# MCU.net
KiCad netlist of a schematic drawn in Altium Designer
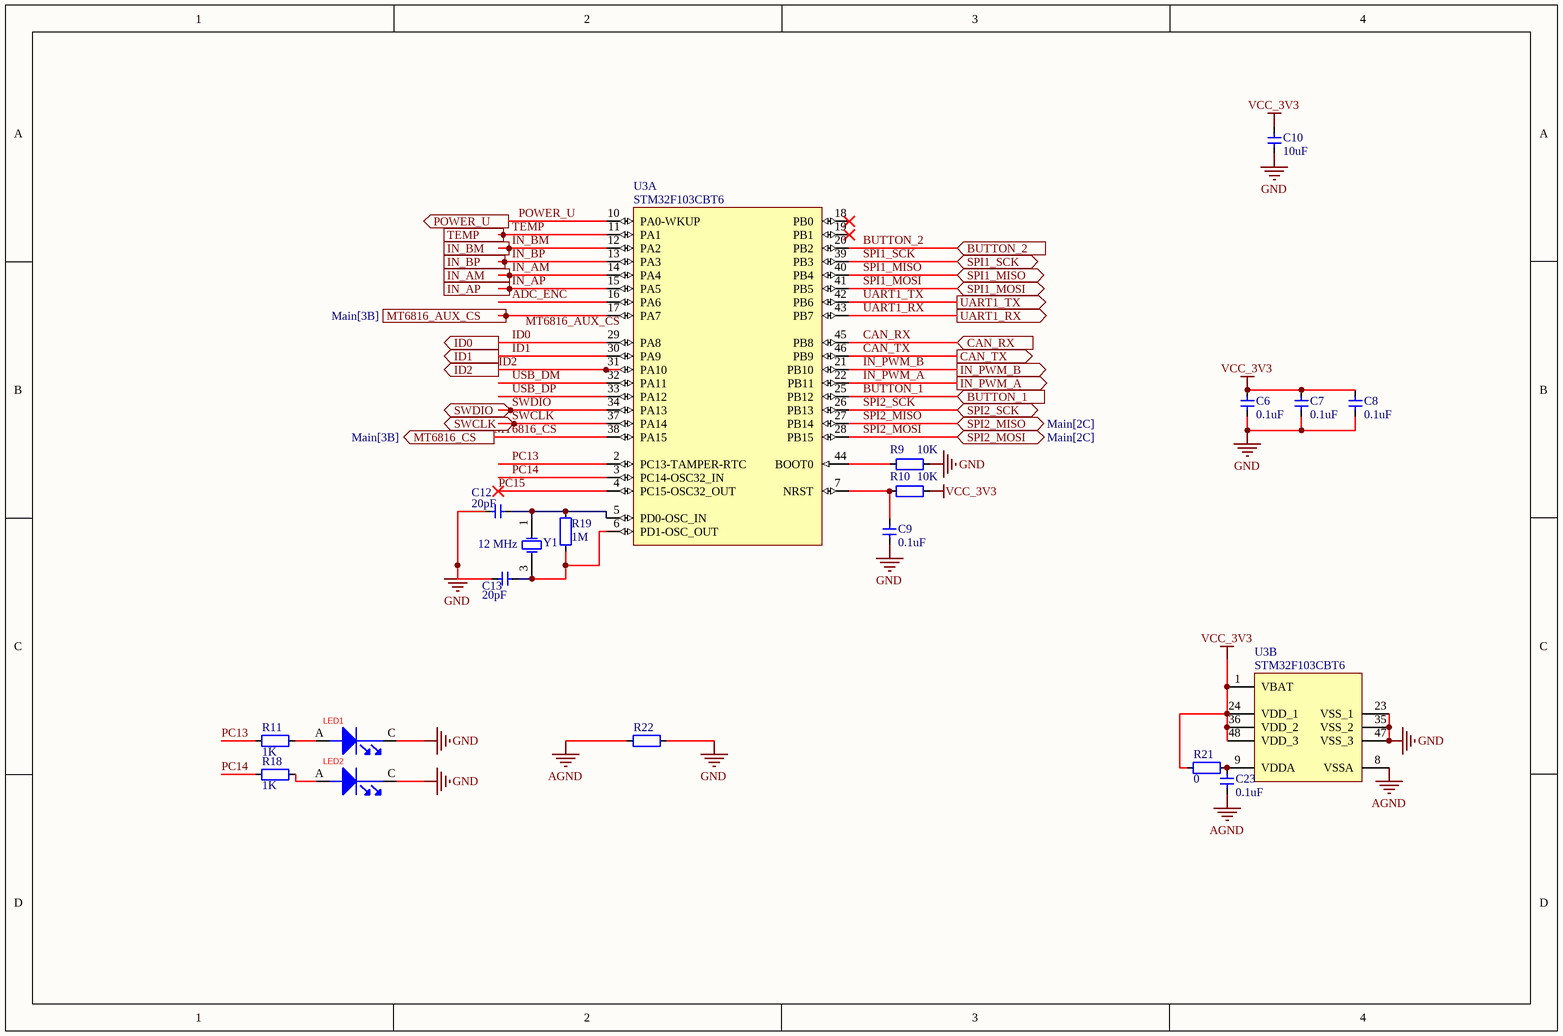
[diagram p0: MCU.SchDoc]

(export (version "E")
  (design (tool "Eeschema 10.0.6"))
  (components
    (comp (ref "C6")
      (value "0.1uF")
      (footprint "motor42-lib:CAP_0402")
      (description "Capacitor")
      (libsource (lib "MyPcbLib") (part "电容-0402"))
    )
    (comp (ref "C7")
      (value "0.1uF")
      (footprint "motor42-lib:CAP_0402")
      (description "Capacitor")
      (libsource (lib "MyPcbLib") (part "电容-0402"))
    )
    (comp (ref "C8")
      (value "0.1uF")
      (footprint "motor42-lib:CAP_0402")
      (description "Capacitor")
      (libsource (lib "MyPcbLib") (part "电容-0402"))
    )
    (comp (ref "C9")
      (value "0.1uF")
      (footprint "motor42-lib:CAP_0402")
      (description "Capacitor")
      (libsource (lib "MyPcbLib") (part "电容-0402"))
    )
    (comp (ref "C10")
      (value "10uF")
      (footprint "CAP_0402")
      (description "Capacitor")
      (libsource (lib "MyPcbLib") (part "电容-0402"))
    )
    (comp (ref "C12")
      (value "20pF")
      (footprint "motor42-lib:CAP_0402")
      (description "Capacitor")
      (libsource (lib "MyPcbLib") (part "电容-0402"))
    )
    (comp (ref "C13")
      (value "20pF")
      (footprint "motor42-lib:CAP_0402")
      (description "Capacitor")
      (libsource (lib "MyPcbLib") (part "电容-0402"))
    )
    (comp (ref "C23")
      (value "0.1uF")
      (footprint "motor42-lib:CAP_0402")
      (description "Capacitor")
      (libsource (lib "MyPcbLib") (part "电容-0402"))
    )
    (comp (ref "LED1")
      (value "LED GREEN")
      (footprint "LED-0603")
      (description "LED GRN SGL RA 25mA 4.1V SMD")
      (libsource (lib "*") (part "LED"))
    )
    (comp (ref "LED2")
      (value "LED GREEN")
      (footprint "LED-0603")
      (description "LED GRN SGL RA 25mA 4.1V SMD")
      (libsource (lib "*") (part "LED"))
    )
    (comp (ref "R9")
      (value "10K")
      (footprint "RES_0402")
      (description "Resistor")
      (libsource (lib "MyPcbLib") (part "电阻-0402"))
    )
    (comp (ref "R10")
      (value "10K")
      (footprint "RES_0402")
      (description "Resistor")
      (libsource (lib "MyPcbLib") (part "电阻-0402"))
    )
    (comp (ref "R11")
      (value "1K")
      (footprint "RES_0402")
      (description "Resistor")
      (libsource (lib "MyPcbLib") (part "电阻-0402"))
    )
    (comp (ref "R18")
      (value "1K")
      (footprint "RES_0402")
      (description "Resistor")
      (libsource (lib "MyPcbLib") (part "电阻-0402"))
    )
    (comp (ref "R19")
      (value "1M")
      (footprint "RES_0402")
      (description "Resistor")
      (libsource (lib "") (part "电阻-0402_1"))
    )
    (comp (ref "R21")
      (value "0")
      (footprint "RES_0402")
      (description "Resistor")
      (libsource (lib "") (part "电阻-0402_2"))
    )
    (comp (ref "R22")
      (value "0")
      (footprint "RES_0402")
      (description "Resistor")
      (libsource (lib "") (part "电阻-0402_2"))
    )
    (comp (ref "U3")
      (value "STM32F103CBT6")
      (footprint "LQFP-48")
      (libsource (lib "STMicroelectronics STM32 F1") (part "STM32F103CBT6"))
    )
    (comp (ref "Y1")
      (value "12 MHz")
      (footprint "LC-SMD-3225_4P")
      (description "Crystal")
      (fields (field (name "Comment") "XTAL-4"))
      (libsource (lib "rpi") (part "XTAL-4"))
    )
  )
  (nets
    (net (code "1") (name "/ADC_ENC") (class "Default")
      (node (ref "U3") (pin "16") (pinfunction "PA6_16") (pintype "bidirectional"))
    )
    (net (code "2") (name "/BUTTON_1") (class "Default")
      (node (ref "U3") (pin "25") (pinfunction "PB12_25") (pintype "bidirectional"))
    )
    (net (code "3") (name "/BUTTON_2") (class "Default")
      (node (ref "U3") (pin "20") (pinfunction "PB2_20") (pintype "bidirectional"))
    )
    (net (code "4") (name "/CAN_RX") (class "Default")
      (node (ref "U3") (pin "45") (pinfunction "PB8_45") (pintype "bidirectional"))
    )
    (net (code "5") (name "/CAN_TX") (class "Default")
      (node (ref "U3") (pin "46") (pinfunction "PB9_46") (pintype "bidirectional"))
    )
    (net (code "6") (name "/ID0") (class "Default")
      (node (ref "U3") (pin "29") (pinfunction "PA8_29") (pintype "bidirectional"))
    )
    (net (code "7") (name "/ID1") (class "Default")
      (node (ref "U3") (pin "30") (pinfunction "PA9_30") (pintype "bidirectional"))
    )
    (net (code "8") (name "/ID2") (class "Default")
      (node (ref "U3") (pin "31") (pinfunction "PA10_31") (pintype "bidirectional"))
    )
    (net (code "9") (name "/IN_AM") (class "Default")
      (node (ref "U3") (pin "14") (pinfunction "PA4_14") (pintype "bidirectional"))
    )
    (net (code "10") (name "/IN_AP") (class "Default")
      (node (ref "U3") (pin "15") (pinfunction "PA5_15") (pintype "bidirectional"))
    )
    (net (code "11") (name "/IN_BM") (class "Default")
      (node (ref "U3") (pin "12") (pinfunction "PA2_12") (pintype "bidirectional"))
    )
    (net (code "12") (name "/IN_BP") (class "Default")
      (node (ref "U3") (pin "13") (pinfunction "PA3_13") (pintype "bidirectional"))
    )
    (net (code "13") (name "/IN_PWM_A") (class "Default")
      (node (ref "U3") (pin "22") (pinfunction "PB11_22") (pintype "bidirectional"))
    )
    (net (code "14") (name "/IN_PWM_B") (class "Default")
      (node (ref "U3") (pin "21") (pinfunction "PB10_21") (pintype "bidirectional"))
    )
    (net (code "15") (name "/MT6816_AUX_CS") (class "Default")
      (node (ref "U3") (pin "17") (pinfunction "PA7_17") (pintype "bidirectional"))
    )
    (net (code "16") (name "/MT6816_CS") (class "Default")
      (node (ref "U3") (pin "38") (pinfunction "PA15_38") (pintype "bidirectional"))
    )
    (net (code "17") (name "/PC13") (class "Default")
      (node (ref "R11") (pin "1") (pinfunction "1_1") (pintype "passive"))
      (node (ref "U3") (pin "2") (pinfunction "PC13-TAMPER-RTC_2") (pintype "bidirectional"))
    )
    (net (code "18") (name "/PC14") (class "Default")
      (node (ref "R18") (pin "1") (pinfunction "1_1") (pintype "passive"))
      (node (ref "U3") (pin "3") (pinfunction "PC14-OSC32_IN_3") (pintype "bidirectional"))
    )
    (net (code "19") (name "/PC15") (class "Default")
      (node (ref "U3") (pin "4") (pinfunction "PC15-OSC32_OUT_4") (pintype "bidirectional+no_connect"))
    )
    (net (code "20") (name "/POWER_U") (class "Default")
      (node (ref "U3") (pin "10") (pinfunction "PA0-WKUP_10") (pintype "bidirectional"))
    )
    (net (code "21") (name "/SPI1_MISO") (class "Default")
      (node (ref "U3") (pin "40") (pinfunction "PB4_40") (pintype "bidirectional"))
    )
    (net (code "22") (name "/SPI1_MOSI") (class "Default")
      (node (ref "U3") (pin "41") (pinfunction "PB5_41") (pintype "bidirectional"))
    )
    (net (code "23") (name "/SPI1_SCK") (class "Default")
      (node (ref "U3") (pin "39") (pinfunction "PB3_39") (pintype "bidirectional"))
    )
    (net (code "24") (name "/SPI2_MISO") (class "Default")
      (node (ref "U3") (pin "27") (pinfunction "PB14_27") (pintype "bidirectional"))
    )
    (net (code "25") (name "/SPI2_MOSI") (class "Default")
      (node (ref "U3") (pin "28") (pinfunction "PB15_28") (pintype "bidirectional"))
    )
    (net (code "26") (name "/SPI2_SCK") (class "Default")
      (node (ref "U3") (pin "26") (pinfunction "PB13_26") (pintype "bidirectional"))
    )
    (net (code "27") (name "/SWCLK") (class "Default")
      (node (ref "U3") (pin "37") (pinfunction "PA14_37") (pintype "bidirectional"))
    )
    (net (code "28") (name "/SWDIO") (class "Default")
      (node (ref "U3") (pin "34") (pinfunction "PA13_34") (pintype "bidirectional"))
    )
    (net (code "29") (name "/TEMP") (class "Default")
      (node (ref "U3") (pin "11") (pinfunction "PA1_11") (pintype "bidirectional"))
    )
    (net (code "30") (name "/UART1_RX") (class "Default")
      (node (ref "U3") (pin "43") (pinfunction "PB7_43") (pintype "bidirectional"))
    )
    (net (code "31") (name "/UART1_TX") (class "Default")
      (node (ref "U3") (pin "42") (pinfunction "PB6_42") (pintype "bidirectional"))
    )
    (net (code "32") (name "/USB_DM") (class "Default")
      (node (ref "U3") (pin "32") (pinfunction "PA11_32") (pintype "bidirectional"))
    )
    (net (code "33") (name "/USB_DP") (class "Default")
      (node (ref "U3") (pin "33") (pinfunction "PA12_33") (pintype "bidirectional"))
    )
    (net (code "34") (name "AGND") (class "Default")
      (node (ref "C23") (pin "1") (pinfunction "1_1") (pintype "passive"))
      (node (ref "R22") (pin "2") (pinfunction "2_2") (pintype "passive"))
      (node (ref "U3") (pin "8") (pinfunction "VSSA_8") (pintype "power_in"))
    )
    (net (code "35") (name "GND") (class "Default")
      (node (ref "C10") (pin "1") (pinfunction "1_1") (pintype "passive"))
      (node (ref "C12") (pin "2") (pinfunction "2_2") (pintype "passive"))
      (node (ref "C13") (pin "2") (pinfunction "2_2") (pintype "passive"))
      (node (ref "C6") (pin "1") (pinfunction "1_1") (pintype "passive"))
      (node (ref "C7") (pin "1") (pinfunction "1_1") (pintype "passive"))
      (node (ref "C8") (pin "1") (pinfunction "1_1") (pintype "passive"))
      (node (ref "C9") (pin "1") (pinfunction "1_1") (pintype "passive"))
      (node (ref "LED1") (pin "C") (pinfunction "CATHODE_C") (pintype "passive"))
      (node (ref "LED2") (pin "C") (pinfunction "CATHODE_C") (pintype "passive"))
      (node (ref "R22") (pin "1") (pinfunction "1_1") (pintype "passive"))
      (node (ref "R9") (pin "2") (pinfunction "2_2") (pintype "passive"))
      (node (ref "U3") (pin "23") (pinfunction "VSS_1_23") (pintype "power_in"))
      (node (ref "U3") (pin "35") (pinfunction "VSS_2_35") (pintype "power_in"))
      (node (ref "U3") (pin "47") (pinfunction "VSS_3_47") (pintype "power_in"))
    )
    (net (code "36") (name "Net-(LED1-ANODE)") (class "Default")
      (node (ref "LED1") (pin "A") (pinfunction "ANODE_A") (pintype "passive"))
      (node (ref "R11") (pin "2") (pinfunction "2_2") (pintype "passive"))
    )
    (net (code "37") (name "Net-(LED2-ANODE)") (class "Default")
      (node (ref "LED2") (pin "A") (pinfunction "ANODE_A") (pintype "passive"))
      (node (ref "R18") (pin "2") (pinfunction "2_2") (pintype "passive"))
    )
    (net (code "38") (name "Net-(U3A-BOOT0)") (class "Default")
      (node (ref "R9") (pin "1") (pinfunction "1_1") (pintype "passive"))
      (node (ref "U3") (pin "44") (pinfunction "BOOT0_44") (pintype "input"))
    )
    (net (code "39") (name "Net-(U3A-NRST)") (class "Default")
      (node (ref "C9") (pin "2") (pinfunction "2_2") (pintype "passive"))
      (node (ref "R10") (pin "1") (pinfunction "1_1") (pintype "passive"))
      (node (ref "U3") (pin "7") (pinfunction "NRST_7") (pintype "bidirectional"))
    )
    (net (code "40") (name "Net-(U3A-PD0-OSC_IN)") (class "Default")
      (node (ref "C12") (pin "1") (pinfunction "1_1") (pintype "passive"))
      (node (ref "R19") (pin "2") (pinfunction "2_2") (pintype "passive"))
      (node (ref "U3") (pin "5") (pinfunction "PD0-OSC_IN_5") (pintype "bidirectional"))
      (node (ref "Y1") (pin "1") (pinfunction "OSC1_1") (pintype "passive"))
    )
    (net (code "41") (name "Net-(U3A-PD1-OSC_OUT)") (class "Default")
      (node (ref "C13") (pin "1") (pinfunction "1_1") (pintype "passive"))
      (node (ref "R19") (pin "1") (pinfunction "1_1") (pintype "passive"))
      (node (ref "U3") (pin "6") (pinfunction "PD1-OSC_OUT_6") (pintype "bidirectional"))
      (node (ref "Y1") (pin "3") (pinfunction "OSC2_3") (pintype "passive"))
    )
    (net (code "42") (name "Net-(U3B-VDDA)") (class "Default")
      (node (ref "C23") (pin "2") (pinfunction "2_2") (pintype "passive"))
      (node (ref "R21") (pin "1") (pinfunction "1_1") (pintype "passive"))
      (node (ref "U3") (pin "9") (pinfunction "VDDA_9") (pintype "power_in"))
    )
    (net (code "43") (name "VCC_3V3") (class "Default")
      (node (ref "C10") (pin "2") (pinfunction "2_2") (pintype "passive"))
      (node (ref "C6") (pin "2") (pinfunction "2_2") (pintype "passive"))
      (node (ref "C7") (pin "2") (pinfunction "2_2") (pintype "passive"))
      (node (ref "C8") (pin "2") (pinfunction "2_2") (pintype "passive"))
      (node (ref "R10") (pin "2") (pinfunction "2_2") (pintype "passive"))
      (node (ref "R21") (pin "2") (pinfunction "2_2") (pintype "passive"))
      (node (ref "U3") (pin "1") (pinfunction "VBAT_1") (pintype "power_in"))
      (node (ref "U3") (pin "24") (pinfunction "VDD_1_24") (pintype "power_in"))
      (node (ref "U3") (pin "36") (pinfunction "VDD_2_36") (pintype "power_in"))
      (node (ref "U3") (pin "48") (pinfunction "VDD_3_48") (pintype "power_in"))
    )
    (net (code "44") (name "unconnected-(U3A-PB0-Pad18)") (class "Default")
      (node (ref "U3") (pin "18") (pinfunction "PB0_18") (pintype "bidirectional+no_connect"))
    )
    (net (code "45") (name "unconnected-(U3A-PB1-Pad19)") (class "Default")
      (node (ref "U3") (pin "19") (pinfunction "PB1_19") (pintype "bidirectional+no_connect"))
    )
  )
)
